# people_counter_v1.net
KiCad netlist of a schematic drawn in EAGLE
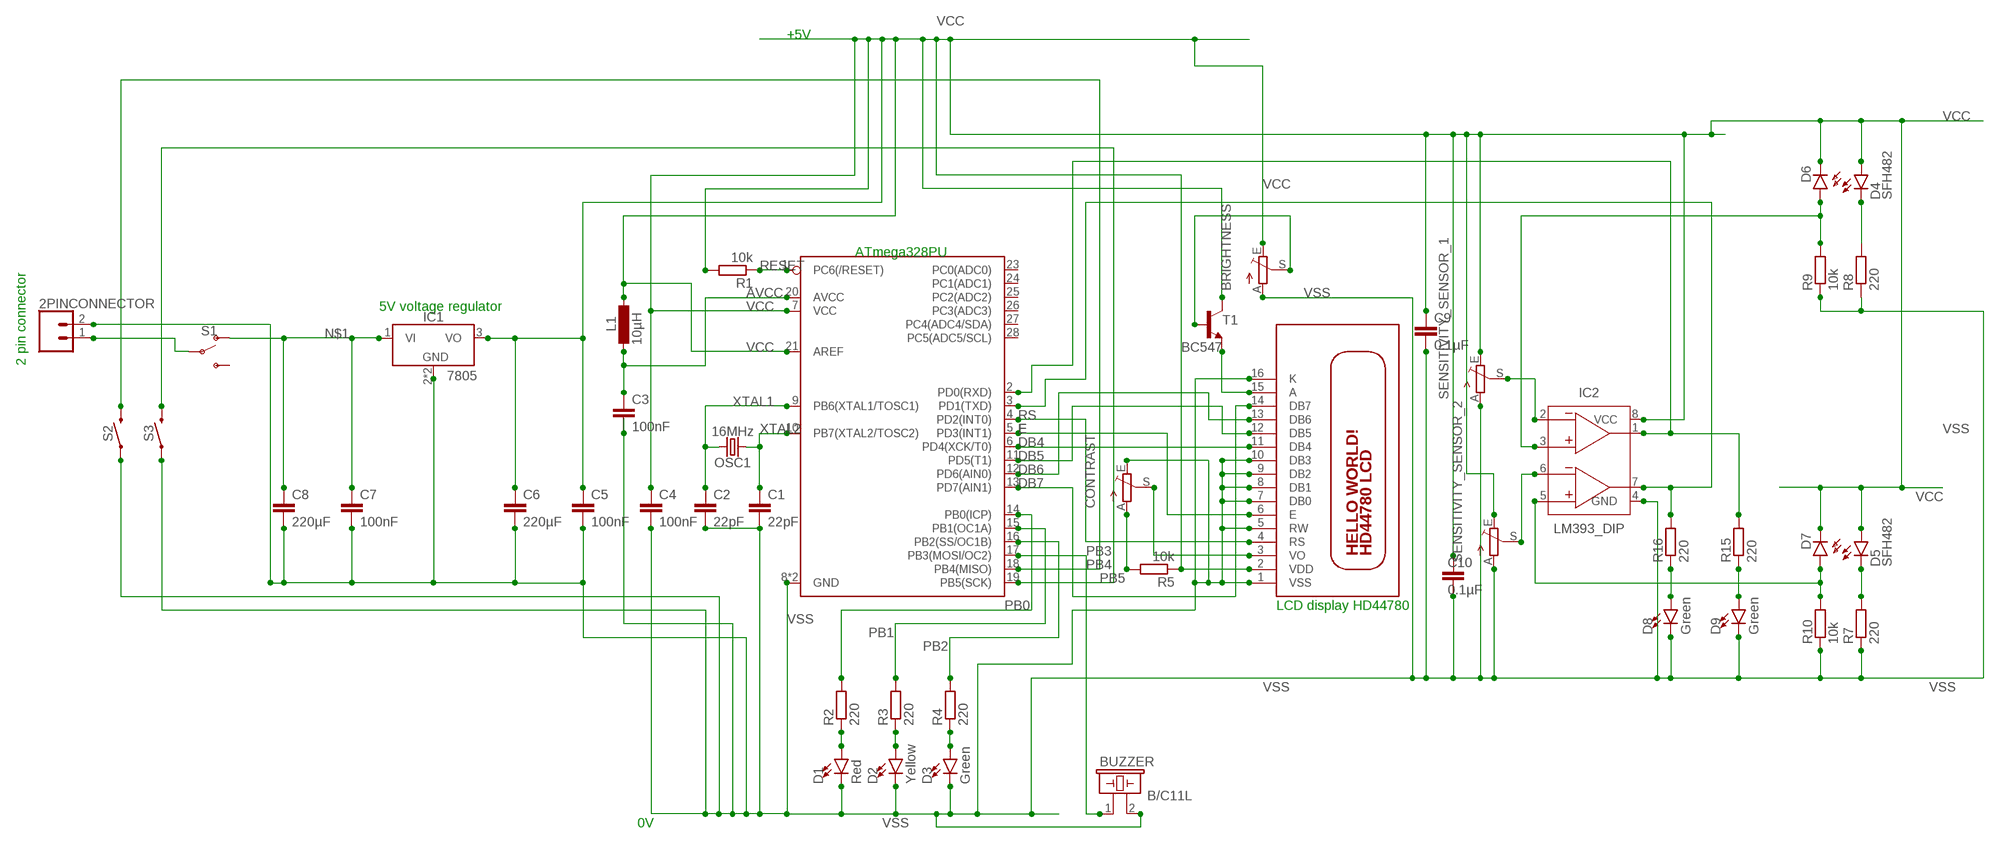
[diagram p0: schematic, sheet 1]

(export (version "E")
  (design (tool "Eeschema 10.0.6"))
  (components
    (comp (ref "2PINCONNECTOR")
      (value "CONN_02")
      (footprint "eagle-import:1X02")
      (libsource (lib "eagle-import") (part "CONN_02"))
    )
    (comp (ref "BRIGHTNESS")
      (value "TRIM_EU-PT10S")
      (footprint "eagle-import:PT-10S")
      (libsource (lib "eagle-import") (part "TRIM_EU-PT10S"))
    )
    (comp (ref "BUZZER")
      (value "B/C11L")
      (footprint "eagle-import:B_C11L")
      (libsource (lib "eagle-import") (part "B/C11L"))
    )
    (comp (ref "C1")
      (value "22pF")
      (footprint "eagle-import:C0805")
      (libsource (lib "eagle-import") (part "C-EUC0805"))
    )
    (comp (ref "C2")
      (value "22pF")
      (footprint "eagle-import:C0805")
      (libsource (lib "eagle-import") (part "C-EUC0805"))
    )
    (comp (ref "C3")
      (value "100nF")
      (footprint "eagle-import:C0805")
      (libsource (lib "eagle-import") (part "C-EUC0805"))
    )
    (comp (ref "C4")
      (value "100nF")
      (footprint "eagle-import:C0805")
      (libsource (lib "eagle-import") (part "C-EUC0805"))
    )
    (comp (ref "C5")
      (value "100nF")
      (footprint "eagle-import:C0805")
      (libsource (lib "eagle-import") (part "C-EUC0805"))
    )
    (comp (ref "C6")
      (value "220µF")
      (footprint "eagle-import:C0805")
      (libsource (lib "eagle-import") (part "C-EUC0805"))
    )
    (comp (ref "C7")
      (value "100nF")
      (footprint "eagle-import:C0805")
      (libsource (lib "eagle-import") (part "C-EUC0805"))
    )
    (comp (ref "C8")
      (value "220µF")
      (footprint "eagle-import:C0805")
      (libsource (lib "eagle-import") (part "C-EUC0805"))
    )
    (comp (ref "C9")
      (value "0.1µF")
      (footprint "eagle-import:C0805")
      (libsource (lib "eagle-import") (part "C-EUC0805"))
    )
    (comp (ref "C10")
      (value "0.1µF")
      (footprint "eagle-import:C0805")
      (libsource (lib "eagle-import") (part "C-EUC0805"))
    )
    (comp (ref "CONTRAST")
      (value "TRIM_EU-PT10S")
      (footprint "eagle-import:PT-10S")
      (libsource (lib "eagle-import") (part "TRIM_EU-PT10S"))
    )
    (comp (ref "D1")
      (value "Red")
      (footprint "eagle-import:LED-0603")
      (libsource (lib "eagle-import") (part "LED-RED-0603-WE"))
    )
    (comp (ref "D2")
      (value "Yellow")
      (footprint "eagle-import:LED-0603")
      (libsource (lib "eagle-import") (part "LED-YELLOW-0603-WE"))
    )
    (comp (ref "D3")
      (value "Green")
      (footprint "eagle-import:LED-0603")
      (libsource (lib "eagle-import") (part "LED-GREEN-0603-WE"))
    )
    (comp (ref "D4")
      (value "SFH482")
      (footprint "eagle-import:SFH482")
      (libsource (lib "eagle-import") (part "SFH482"))
    )
    (comp (ref "D5")
      (value "SFH482")
      (footprint "eagle-import:SFH482")
      (libsource (lib "eagle-import") (part "SFH482"))
    )
    (comp (ref "D6")
      (value "BP104")
      (footprint "eagle-import:BP104")
      (fields (field (name "MF") "VISHAY/TELEFUNKEN"))
      (libsource (lib "eagle-import") (part "BP104"))
    )
    (comp (ref "D7")
      (value "BP104")
      (footprint "eagle-import:BP104")
      (fields (field (name "MF") "VISHAY/TELEFUNKEN"))
      (libsource (lib "eagle-import") (part "BP104"))
    )
    (comp (ref "D8")
      (value "Green")
      (footprint "eagle-import:LED-0603")
      (libsource (lib "eagle-import") (part "LED-GREEN-0603-WE"))
    )
    (comp (ref "D9")
      (value "Green")
      (footprint "eagle-import:LED-0603")
      (libsource (lib "eagle-import") (part "LED-GREEN-0603-WE"))
    )
    (comp (ref "IC1")
      (value "7805")
      (footprint "eagle-import:SOT230P700X170-4")
      (fields (field (name "MANUFACTURER") "Generic"))
      (libsource (lib "eagle-import") (part "LM7805_SOT223"))
    )
    (comp (ref "IC2")
      (value "LM393_DIP")
      (footprint "eagle-import:DIP826W53P254L959H508Q8B")
      (libsource (lib "eagle-import") (part "LM393_DIP"))
    )
    (comp (ref "L1")
      (value "10µH")
      (footprint "eagle-import:L1812")
      (libsource (lib "eagle-import") (part "L-EUL1812"))
    )
    (comp (ref "OSC1")
      (value "16MHz")
      (footprint "eagle-import:HC49US")
      (libsource (lib "eagle-import") (part "CRYSTAL-16MHZPTH-HC49US"))
    )
    (comp (ref "R1")
      (value "10k")
      (footprint "eagle-import:R0603")
      (libsource (lib "eagle-import") (part "R-EU_R0603"))
    )
    (comp (ref "R2")
      (value "220")
      (footprint "eagle-import:R0603")
      (libsource (lib "eagle-import") (part "R-EU_R0603"))
    )
    (comp (ref "R3")
      (value "220")
      (footprint "eagle-import:R0603")
      (libsource (lib "eagle-import") (part "R-EU_R0603"))
    )
    (comp (ref "R4")
      (value "220")
      (footprint "eagle-import:R0603")
      (libsource (lib "eagle-import") (part "R-EU_R0603"))
    )
    (comp (ref "R5")
      (value "10k")
      (footprint "eagle-import:R0603")
      (libsource (lib "eagle-import") (part "R-EU_R0603"))
    )
    (comp (ref "R7")
      (value "220")
      (footprint "eagle-import:R0603")
      (libsource (lib "eagle-import") (part "R-EU_R0603"))
    )
    (comp (ref "R8")
      (value "220")
      (footprint "eagle-import:R0603")
      (libsource (lib "eagle-import") (part "R-EU_R0603"))
    )
    (comp (ref "R9")
      (value "10k")
      (footprint "eagle-import:R0603")
      (libsource (lib "eagle-import") (part "R-EU_R0603"))
    )
    (comp (ref "R10")
      (value "10k")
      (footprint "eagle-import:R0603")
      (libsource (lib "eagle-import") (part "R-EU_R0603"))
    )
    (comp (ref "R15")
      (value "220")
      (footprint "eagle-import:R0603")
      (libsource (lib "eagle-import") (part "R-EU_R0603"))
    )
    (comp (ref "R16")
      (value "220")
      (footprint "eagle-import:R0603")
      (libsource (lib "eagle-import") (part "R-EU_R0603"))
    )
    (comp (ref "S1")
      (value "SWITCH-SPDT-PTH-11.6X4.0MM")
      (footprint "eagle-import:SWITCH_SPDT_PTH_11.6X4.0MM")
      (libsource (lib "eagle-import") (part "SWITCH-SPDT-PTH-11.6X4.0MM"))
    )
    (comp (ref "S2")
      (value "MOMENTARY-SWITCH-SPST-PTH-6.0MM")
      (footprint "eagle-import:TACTILE_SWITCH_PTH_6.0MM")
      (libsource (lib "eagle-import") (part "MOMENTARY-SWITCH-SPST-PTH-6.0MM"))
    )
    (comp (ref "S3")
      (value "MOMENTARY-SWITCH-SPST-PTH-6.0MM")
      (footprint "eagle-import:TACTILE_SWITCH_PTH_6.0MM")
      (libsource (lib "eagle-import") (part "MOMENTARY-SWITCH-SPST-PTH-6.0MM"))
    )
    (comp (ref "SENSITIVITY_SENSOR_1")
      (value "TRIM_EU-PT10S")
      (footprint "eagle-import:PT-10S")
      (libsource (lib "eagle-import") (part "TRIM_EU-PT10S"))
    )
    (comp (ref "SENSITIVITY_SENSOR_2")
      (value "TRIM_EU-PT10S")
      (footprint "eagle-import:PT-10S")
      (libsource (lib "eagle-import") (part "TRIM_EU-PT10S"))
    )
    (comp (ref "T1")
      (value "BC547")
      (footprint "eagle-import:TO92")
      (libsource (lib "eagle-import") (part "BC547"))
    )
    (comp (ref "U1")
      (value "328P")
      (footprint "eagle-import:DIP28")
      (libsource (lib "eagle-import") (part "ATMEGA328P_PDIP"))
    )
    (comp (ref "X1")
      (value "HD44780LCD-1602")
      (footprint "eagle-import:LCD1602")
      (libsource (lib "eagle-import") (part "HD44780LCD-1602"))
    )
  )
  (nets
    (net (code "1") (name "AVCC") (class "Default")
      (node (ref "C3") (pin "1") (pinfunction "1_1") (pintype "passive"))
      (node (ref "L1") (pin "2") (pinfunction "2_2") (pintype "passive"))
      (node (ref "U1") (pin "20") (pinfunction "AVCC_20") (pintype "bidirectional"))
    )
    (net (code "2") (name "DB4") (class "Default")
      (node (ref "U1") (pin "6") (pinfunction "PD4(XCK/T0)_6") (pintype "bidirectional"))
      (node (ref "X1") (pin "11") (pinfunction "DB4_11") (pintype "bidirectional"))
    )
    (net (code "3") (name "DB5") (class "Default")
      (node (ref "U1") (pin "11") (pinfunction "PD5(T1)_11") (pintype "bidirectional"))
      (node (ref "X1") (pin "12") (pinfunction "DB5_12") (pintype "bidirectional"))
    )
    (net (code "4") (name "DB6") (class "Default")
      (node (ref "U1") (pin "12") (pinfunction "PD6(AIN0)_12") (pintype "bidirectional"))
      (node (ref "X1") (pin "13") (pinfunction "DB6_13") (pintype "bidirectional"))
    )
    (net (code "5") (name "DB7") (class "Default")
      (node (ref "U1") (pin "13") (pinfunction "PD7(AIN1)_13") (pintype "bidirectional"))
      (node (ref "X1") (pin "14") (pinfunction "DB7_14") (pintype "bidirectional"))
    )
    (net (code "6") (name "E") (class "Default")
      (node (ref "U1") (pin "5") (pinfunction "PD3(INT1)_5") (pintype "bidirectional"))
      (node (ref "X1") (pin "6") (pinfunction "E_6") (pintype "input"))
    )
    (net (code "7") (name "N$1") (class "Default")
      (node (ref "C7") (pin "1") (pinfunction "1_1") (pintype "passive"))
      (node (ref "C8") (pin "1") (pinfunction "1_1") (pintype "passive"))
      (node (ref "IC1") (pin "1") (pinfunction "VI_1") (pintype "input"))
      (node (ref "S1") (pin "1") (pinfunction "O_1") (pintype "passive"))
    )
    (net (code "8") (name "Net-(CONTRAST-PadA)") (class "Default")
      (node (ref "CONTRAST") (pin "A") (pinfunction "A_A") (pintype "passive"))
      (node (ref "R5") (pin "2") (pinfunction "2_2") (pintype "passive"))
    )
    (net (code "9") (name "Net-(D1-PadA)") (class "Default")
      (node (ref "D1") (pin "A") (pinfunction "A_A") (pintype "passive"))
      (node (ref "R2") (pin "1") (pinfunction "1_1") (pintype "passive"))
    )
    (net (code "10") (name "Net-(D2-PadA)") (class "Default")
      (node (ref "D2") (pin "A") (pinfunction "A_A") (pintype "passive"))
      (node (ref "R3") (pin "1") (pinfunction "1_1") (pintype "passive"))
    )
    (net (code "11") (name "Net-(D3-PadA)") (class "Default")
      (node (ref "D3") (pin "A") (pinfunction "A_A") (pintype "passive"))
      (node (ref "R4") (pin "1") (pinfunction "1_1") (pintype "passive"))
    )
    (net (code "12") (name "Net-(D4-C)") (class "Default")
      (node (ref "D4") (pin "K") (pinfunction "C_K") (pintype "passive"))
      (node (ref "R8") (pin "2") (pinfunction "2_2") (pintype "passive"))
    )
    (net (code "13") (name "Net-(D5-C)") (class "Default")
      (node (ref "D5") (pin "K") (pinfunction "C_K") (pintype "passive"))
      (node (ref "R7") (pin "2") (pinfunction "2_2") (pintype "passive"))
    )
    (net (code "14") (name "Net-(D8-PadA)") (class "Default")
      (node (ref "D8") (pin "A") (pinfunction "A_A") (pintype "passive"))
      (node (ref "R16") (pin "1") (pinfunction "1_1") (pintype "passive"))
    )
    (net (code "15") (name "Net-(D9-PadA)") (class "Default")
      (node (ref "D9") (pin "A") (pinfunction "A_A") (pintype "passive"))
      (node (ref "R15") (pin "1") (pinfunction "1_1") (pintype "passive"))
    )
    (net (code "16") (name "Net-(IC2-+IN1)") (class "Default")
      (node (ref "D6") (pin "A") (pinfunction "A_A") (pintype "passive"))
      (node (ref "IC2") (pin "3") (pinfunction "+IN1_3") (pintype "input"))
      (node (ref "R9") (pin "2") (pinfunction "2_2") (pintype "passive"))
    )
    (net (code "17") (name "Net-(IC2-+IN2)") (class "Default")
      (node (ref "D7") (pin "A") (pinfunction "A_A") (pintype "passive"))
      (node (ref "IC2") (pin "5") (pinfunction "+IN2_5") (pintype "input"))
      (node (ref "R10") (pin "2") (pinfunction "2_2") (pintype "passive"))
    )
    (net (code "18") (name "Net-(IC2--IN1)") (class "Default")
      (node (ref "IC2") (pin "2") (pinfunction "-IN1_2") (pintype "input"))
      (node (ref "SENSITIVITY_SENSOR_1") (pin "S") (pinfunction "S_S") (pintype "passive"))
    )
    (net (code "19") (name "Net-(IC2--IN2)") (class "Default")
      (node (ref "IC2") (pin "6") (pinfunction "-IN2_6") (pintype "input"))
      (node (ref "SENSITIVITY_SENSOR_2") (pin "S") (pinfunction "S_S") (pintype "passive"))
    )
    (net (code "20") (name "Net-(IC2-OUT1)") (class "Default")
      (node (ref "IC2") (pin "1") (pinfunction "OUT1_1") (pintype "output"))
      (node (ref "R15") (pin "2") (pinfunction "2_2") (pintype "passive"))
      (node (ref "U1") (pin "2") (pinfunction "PD0(RXD)_2") (pintype "bidirectional"))
    )
    (net (code "21") (name "Net-(IC2-OUT2)") (class "Default")
      (node (ref "IC2") (pin "7") (pinfunction "OUT2_7") (pintype "output"))
      (node (ref "R16") (pin "2") (pinfunction "2_2") (pintype "passive"))
      (node (ref "U1") (pin "3") (pinfunction "PD1(TXD)_3") (pintype "bidirectional"))
    )
    (net (code "22") (name "Net-(S1-P)") (class "Default")
      (node (ref "2PINCONNECTOR") (pin "1") (pinfunction "1_1") (pintype "passive"))
      (node (ref "S1") (pin "2") (pinfunction "P_2") (pintype "passive"))
    )
    (net (code "23") (name "Net-(T1-B)") (class "Default")
      (node (ref "BRIGHTNESS") (pin "S") (pinfunction "S_S") (pintype "passive"))
      (node (ref "T1") (pin "2") (pinfunction "B_2") (pintype "passive"))
    )
    (net (code "24") (name "Net-(T1-E)") (class "Default")
      (node (ref "T1") (pin "1") (pinfunction "E_1") (pintype "passive"))
      (node (ref "X1") (pin "15") (pinfunction "A_15") (pintype "input"))
    )
    (net (code "25") (name "Net-(X1-VO)") (class "Default")
      (node (ref "CONTRAST") (pin "S") (pinfunction "S_S") (pintype "passive"))
      (node (ref "X1") (pin "3") (pinfunction "VO_3") (pintype "input"))
    )
    (net (code "26") (name "PB0") (class "Default")
      (node (ref "R2") (pin "2") (pinfunction "2_2") (pintype "passive"))
      (node (ref "U1") (pin "14") (pinfunction "PB0(ICP)_14") (pintype "bidirectional"))
    )
    (net (code "27") (name "PB1") (class "Default")
      (node (ref "R3") (pin "2") (pinfunction "2_2") (pintype "passive"))
      (node (ref "U1") (pin "15") (pinfunction "PB1(OC1A)_15") (pintype "bidirectional"))
    )
    (net (code "28") (name "PB2") (class "Default")
      (node (ref "R4") (pin "2") (pinfunction "2_2") (pintype "passive"))
      (node (ref "U1") (pin "16") (pinfunction "PB2(SS/OC1B)_16") (pintype "bidirectional"))
    )
    (net (code "29") (name "PB3") (class "Default")
      (node (ref "BUZZER") (pin "1") (pinfunction "1_1") (pintype "passive"))
      (node (ref "U1") (pin "17") (pinfunction "PB3(MOSI/OC2)_17") (pintype "bidirectional"))
    )
    (net (code "30") (name "PB4") (class "Default")
      (node (ref "S2") (pin "3") (pinfunction "2_3") (pintype "passive"))
      (node (ref "U1") (pin "18") (pinfunction "PB4(MISO)_18") (pintype "bidirectional"))
    )
    (net (code "31") (name "PB5") (class "Default")
      (node (ref "S3") (pin "3") (pinfunction "2_3") (pintype "passive"))
      (node (ref "U1") (pin "19") (pinfunction "PB5(SCK)_19") (pintype "bidirectional"))
    )
    (net (code "32") (name "RESET") (class "Default")
      (node (ref "R1") (pin "1") (pinfunction "1_1") (pintype "passive"))
      (node (ref "U1") (pin "1") (pinfunction "PC6(/RESET)_1") (pintype "bidirectional"))
    )
    (net (code "33") (name "RS") (class "Default")
      (node (ref "U1") (pin "4") (pinfunction "PD2(INT0)_4") (pintype "bidirectional"))
      (node (ref "X1") (pin "4") (pinfunction "RS_4") (pintype "input"))
    )
    (net (code "34") (name "VCC") (class "Default")
      (node (ref "BRIGHTNESS") (pin "E") (pinfunction "E_E") (pintype "passive"))
      (node (ref "C10") (pin "1") (pinfunction "1_1") (pintype "passive"))
      (node (ref "C4") (pin "1") (pinfunction "1_1") (pintype "passive"))
      (node (ref "C5") (pin "1") (pinfunction "1_1") (pintype "passive"))
      (node (ref "C6") (pin "1") (pinfunction "1_1") (pintype "passive"))
      (node (ref "C9") (pin "1") (pinfunction "1_1") (pintype "passive"))
      (node (ref "D4") (pin "A") (pinfunction "A_A") (pintype "passive"))
      (node (ref "D5") (pin "A") (pinfunction "A_A") (pintype "passive"))
      (node (ref "D6") (pin "K") (pinfunction "C_K") (pintype "passive"))
      (node (ref "D7") (pin "K") (pinfunction "C_K") (pintype "passive"))
      (node (ref "IC1") (pin "3") (pinfunction "VO_3") (pintype "output"))
      (node (ref "IC2") (pin "8") (pinfunction "VCC_8") (pintype "bidirectional"))
      (node (ref "L1") (pin "1") (pinfunction "1_1") (pintype "passive"))
      (node (ref "R1") (pin "2") (pinfunction "2_2") (pintype "passive"))
      (node (ref "R5") (pin "1") (pinfunction "1_1") (pintype "passive"))
      (node (ref "SENSITIVITY_SENSOR_1") (pin "E") (pinfunction "E_E") (pintype "passive"))
      (node (ref "SENSITIVITY_SENSOR_2") (pin "E") (pinfunction "E_E") (pintype "passive"))
      (node (ref "T1") (pin "3") (pinfunction "C_3") (pintype "passive"))
      (node (ref "U1") (pin "21") (pinfunction "AREF_21") (pintype "bidirectional"))
      (node (ref "U1") (pin "7") (pinfunction "VCC_7") (pintype "bidirectional"))
      (node (ref "X1") (pin "2") (pinfunction "VDD_2") (pintype "power_in"))
    )
    (net (code "35") (name "VSS") (class "Default")
      (node (ref "2PINCONNECTOR") (pin "2") (pinfunction "2_2") (pintype "passive"))
      (node (ref "BRIGHTNESS") (pin "A") (pinfunction "A_A") (pintype "passive"))
      (node (ref "BUZZER") (pin "2") (pinfunction "2_2") (pintype "passive"))
      (node (ref "C1") (pin "2") (pinfunction "2_2") (pintype "passive"))
      (node (ref "C10") (pin "2") (pinfunction "2_2") (pintype "passive"))
      (node (ref "C2") (pin "2") (pinfunction "2_2") (pintype "passive"))
      (node (ref "C3") (pin "2") (pinfunction "2_2") (pintype "passive"))
      (node (ref "C4") (pin "2") (pinfunction "2_2") (pintype "passive"))
      (node (ref "C5") (pin "2") (pinfunction "2_2") (pintype "passive"))
      (node (ref "C6") (pin "2") (pinfunction "2_2") (pintype "passive"))
      (node (ref "C7") (pin "2") (pinfunction "2_2") (pintype "passive"))
      (node (ref "C8") (pin "2") (pinfunction "2_2") (pintype "passive"))
      (node (ref "C9") (pin "2") (pinfunction "2_2") (pintype "passive"))
      (node (ref "CONTRAST") (pin "E") (pinfunction "E_E") (pintype "passive"))
      (node (ref "D1") (pin "C") (pinfunction "C_C") (pintype "passive"))
      (node (ref "D2") (pin "C") (pinfunction "C_C") (pintype "passive"))
      (node (ref "D3") (pin "C") (pinfunction "C_C") (pintype "passive"))
      (node (ref "D8") (pin "C") (pinfunction "C_C") (pintype "passive"))
      (node (ref "D9") (pin "C") (pinfunction "C_C") (pintype "passive"))
      (node (ref "IC1") (pin "2") (pinfunction "GND_2") (pintype "passive"))
      (node (ref "IC1") (pin "4") (pinfunction "GND_4") (pintype "passive"))
      (node (ref "IC2") (pin "4") (pinfunction "GND_4") (pintype "bidirectional"))
      (node (ref "R10") (pin "1") (pinfunction "1_1") (pintype "passive"))
      (node (ref "R7") (pin "1") (pinfunction "1_1") (pintype "passive"))
      (node (ref "R8") (pin "1") (pinfunction "1_1") (pintype "passive"))
      (node (ref "R9") (pin "1") (pinfunction "1_1") (pintype "passive"))
      (node (ref "S2") (pin "1") (pinfunction "1_1") (pintype "passive"))
      (node (ref "S3") (pin "1") (pinfunction "1_1") (pintype "passive"))
      (node (ref "SENSITIVITY_SENSOR_1") (pin "A") (pinfunction "A_A") (pintype "passive"))
      (node (ref "SENSITIVITY_SENSOR_2") (pin "A") (pinfunction "A_A") (pintype "passive"))
      (node (ref "U1") (pin "22") (pinfunction "GND_22") (pintype "bidirectional"))
      (node (ref "U1") (pin "8") (pinfunction "GND_8") (pintype "bidirectional"))
      (node (ref "X1") (pin "1") (pinfunction "VSS_1") (pintype "power_in"))
      (node (ref "X1") (pin "10") (pinfunction "DB3_10") (pintype "bidirectional"))
      (node (ref "X1") (pin "16") (pinfunction "K_16") (pintype "input"))
      (node (ref "X1") (pin "5") (pinfunction "RW_5") (pintype "input"))
      (node (ref "X1") (pin "7") (pinfunction "DB0_7") (pintype "bidirectional"))
      (node (ref "X1") (pin "8") (pinfunction "DB1_8") (pintype "bidirectional"))
      (node (ref "X1") (pin "9") (pinfunction "DB2_9") (pintype "bidirectional"))
    )
    (net (code "36") (name "XTAL1") (class "Default")
      (node (ref "C2") (pin "1") (pinfunction "1_1") (pintype "passive"))
      (node (ref "OSC1") (pin "2") (pinfunction "2_2") (pintype "passive"))
      (node (ref "U1") (pin "9") (pinfunction "PB6(XTAL1/TOSC1)_9") (pintype "bidirectional"))
    )
    (net (code "37") (name "XTAL2") (class "Default")
      (node (ref "C1") (pin "1") (pinfunction "1_1") (pintype "passive"))
      (node (ref "OSC1") (pin "1") (pinfunction "1_1") (pintype "passive"))
      (node (ref "U1") (pin "10") (pinfunction "PB7(XTAL2/TOSC2)_10") (pintype "bidirectional"))
    )
    (net (code "38") (name "unconnected-(S1-S-Pad3)") (class "Default")
      (node (ref "S1") (pin "3") (pinfunction "S_3") (pintype "passive"))
    )
    (net (code "39") (name "unconnected-(U1-PC0(ADC0)-Pad23)") (class "Default")
      (node (ref "U1") (pin "23") (pinfunction "PC0(ADC0)_23") (pintype "bidirectional"))
    )
    (net (code "40") (name "unconnected-(U1-PC1(ADC1)-Pad24)") (class "Default")
      (node (ref "U1") (pin "24") (pinfunction "PC1(ADC1)_24") (pintype "bidirectional"))
    )
    (net (code "41") (name "unconnected-(U1-PC2(ADC2)-Pad25)") (class "Default")
      (node (ref "U1") (pin "25") (pinfunction "PC2(ADC2)_25") (pintype "bidirectional"))
    )
    (net (code "42") (name "unconnected-(U1-PC3(ADC3)-Pad26)") (class "Default")
      (node (ref "U1") (pin "26") (pinfunction "PC3(ADC3)_26") (pintype "bidirectional"))
    )
    (net (code "43") (name "unconnected-(U1-PC4(ADC4{slash}SDA)-Pad27)") (class "Default")
      (node (ref "U1") (pin "27") (pinfunction "PC4(ADC4/SDA)_27") (pintype "bidirectional"))
    )
    (net (code "44") (name "unconnected-(U1-PC5(ADC5{slash}SCL)-Pad28)") (class "Default")
      (node (ref "U1") (pin "28") (pinfunction "PC5(ADC5/SCL)_28") (pintype "bidirectional"))
    )
  )
)
